# Sheet2.net
KiCad netlist of a schematic drawn in Altium Designer
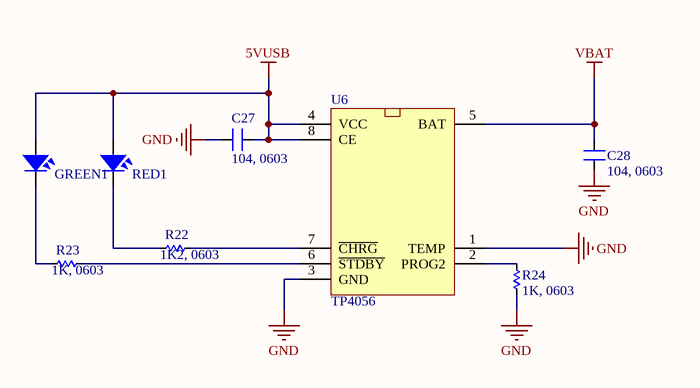
[diagram p0: Sheet2.SchDoc]

(export (version "E")
  (design (tool "Eeschema 10.0.6"))
  (components
    (comp (ref "C27")
      (value "104, 0603")
      (footprint "SM-0603")
      (description "Cap SMD")
      (libsource (lib "KhanhBK_Library_4") (part "CM"))
    )
    (comp (ref "C28")
      (value "104, 0603")
      (footprint "SM-0603")
      (description "Cap SMD")
      (libsource (lib "KhanhBK_Library_4") (part "CM"))
    )
    (comp (ref "GREEN1")
      (value "LED")
      (footprint "LED-0805-Blue")
      (libsource (lib "KhanhBK_SCH_Library_1") (part "LED SMD"))
    )
    (comp (ref "R22")
      (value "1K2, 0603")
      (footprint "RES-SMD-0603")
      (description "Resistor")
      (fields
        (field (name "MANUFACTURER") "Generic Components")
        (field (name "PUBLISHER") "Altium Hobart Technology Centre")
      )
      (libsource (lib "KhanhBK_SCH_Library_1") (part "Res-SMD"))
    )
    (comp (ref "R23")
      (value "1K, 0603")
      (footprint "RES-SMD-0603")
      (description "Resistor")
      (fields
        (field (name "MANUFACTURER") "Generic Components")
        (field (name "PUBLISHER") "Altium Hobart Technology Centre")
      )
      (libsource (lib "KhanhBK_SCH_Library_1") (part "Res-SMD"))
    )
    (comp (ref "R24")
      (value "1K, 0603")
      (footprint "RES-SMD-0603")
      (description "Resistor")
      (fields
        (field (name "MANUFACTURER") "Generic Components")
        (field (name "PUBLISHER") "Altium Hobart Technology Centre")
      )
      (libsource (lib "KhanhBK_SCH_Library_1") (part "Res-SMD"))
    )
    (comp (ref "RED1")
      (value "LED")
      (footprint "LED-0805-Blue")
      (libsource (lib "KhanhBK_SCH_Library_1") (part "LED SMD"))
    )
    (comp (ref "U6")
      (value "TP4056")
      (footprint "MinhTien_PcbLib:SOP8_L")
      (description "1A Standalone Linear Li-lon Battery Charger with Thermal   Regulation")
      (libsource (lib "KhanhBK_SCH_Lib_5") (part "TP4056"))
    )
  )
  (nets
    (net (code "1") (name "5VUSB") (class "Default")
      (node (ref "C27") (pin "1") (pinfunction "1_1") (pintype "passive"))
      (node (ref "GREEN1") (pin "1") (pinfunction "1_1") (pintype "passive"))
      (node (ref "RED1") (pin "1") (pinfunction "1_1") (pintype "passive"))
      (node (ref "U6") (pin "4") (pinfunction "VCC_4") (pintype "passive"))
      (node (ref "U6") (pin "8") (pinfunction "CE_8") (pintype "passive"))
    )
    (net (code "2") (name "GND") (class "Default")
      (node (ref "C27") (pin "2") (pinfunction "2_2") (pintype "passive"))
      (node (ref "C28") (pin "2") (pinfunction "2_2") (pintype "passive"))
      (node (ref "R24") (pin "2") (pinfunction "2_2") (pintype "passive"))
      (node (ref "U6") (pin "1") (pinfunction "TEMP_1") (pintype "passive"))
      (node (ref "U6") (pin "3") (pinfunction "GND_3") (pintype "passive"))
    )
    (net (code "3") (name "Net-(GREEN1-Pad2)") (class "Default")
      (node (ref "GREEN1") (pin "2") (pinfunction "2_2") (pintype "passive"))
      (node (ref "R23") (pin "2") (pinfunction "2_2") (pintype "passive"))
    )
    (net (code "4") (name "Net-(R22-Pad2)") (class "Default")
      (node (ref "R22") (pin "2") (pinfunction "2_2") (pintype "passive"))
      (node (ref "RED1") (pin "2") (pinfunction "2_2") (pintype "passive"))
    )
    (net (code "5") (name "Net-(U6-PROG2)") (class "Default")
      (node (ref "R24") (pin "1") (pinfunction "1_1") (pintype "passive"))
      (node (ref "U6") (pin "2") (pinfunction "PROG2_2") (pintype "passive"))
    )
    (net (code "6") (name "Net-(U6-~{CHRG})") (class "Default")
      (node (ref "R22") (pin "1") (pinfunction "1_1") (pintype "passive"))
      (node (ref "U6") (pin "7") (pinfunction "~{CHRG}_7") (pintype "passive"))
    )
    (net (code "7") (name "Net-(U6-~{STDBY})") (class "Default")
      (node (ref "R23") (pin "1") (pinfunction "1_1") (pintype "passive"))
      (node (ref "U6") (pin "6") (pinfunction "~{STDBY}_6") (pintype "passive"))
    )
    (net (code "8") (name "VBAT") (class "Default")
      (node (ref "C28") (pin "1") (pinfunction "1_1") (pintype "passive"))
      (node (ref "U6") (pin "5") (pinfunction "BAT_5") (pintype "passive"))
    )
  )
)
